# cc1200_wisun_st.net
KiCad netlist of a schematic drawn in Altium Designer
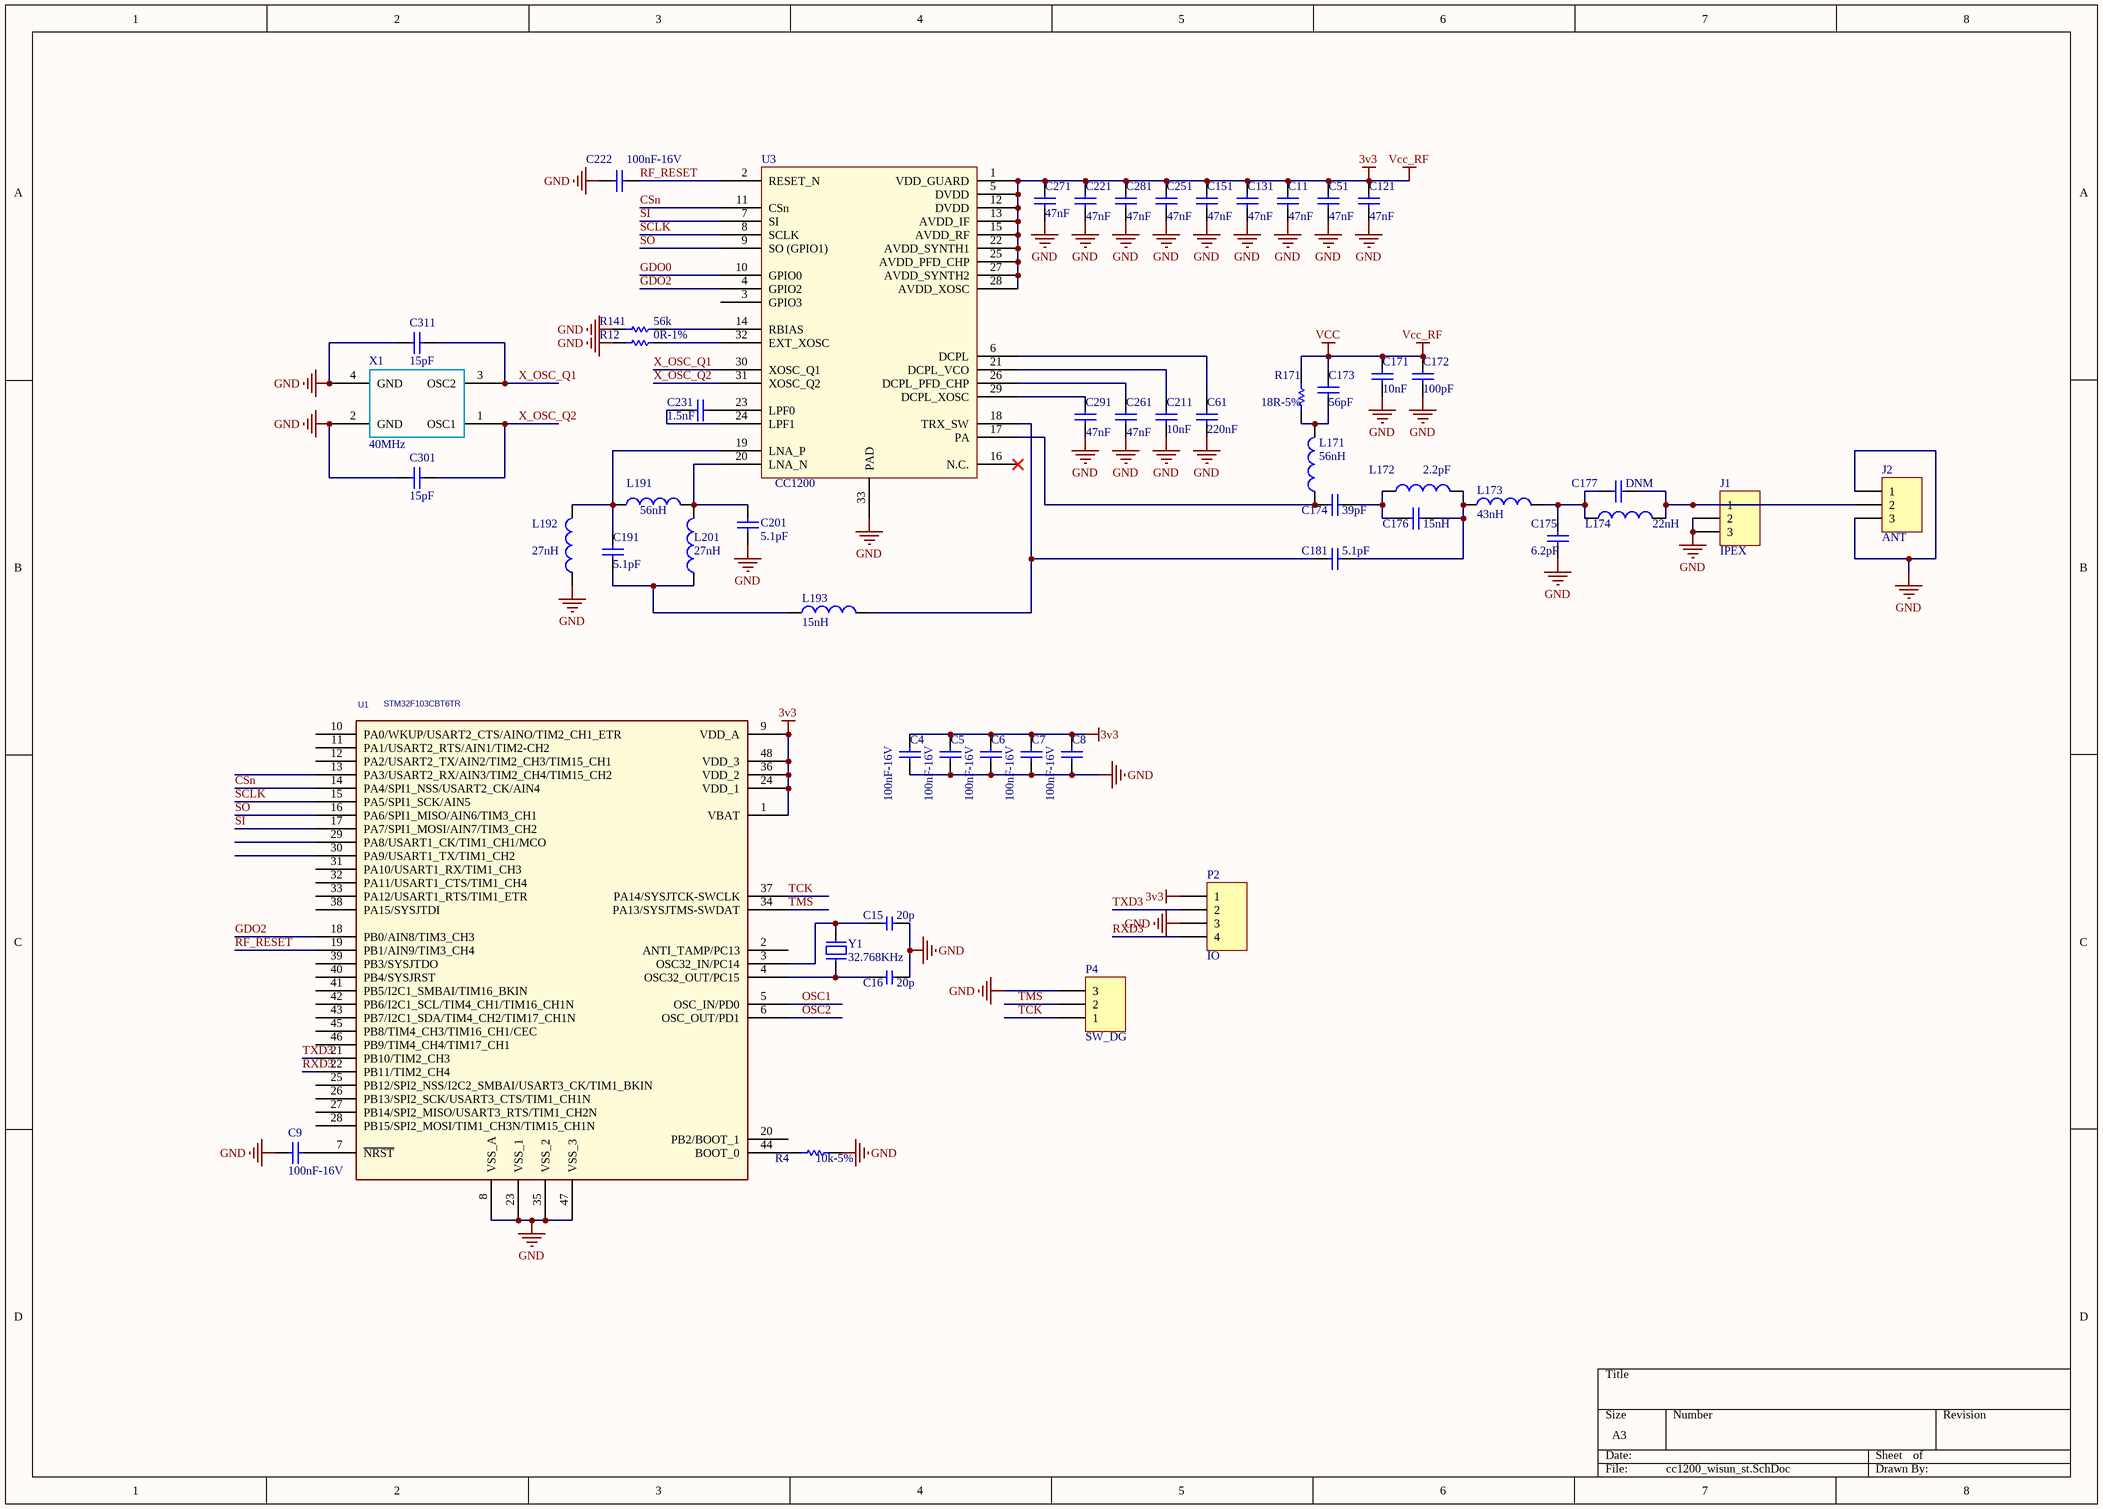
[diagram p0: cc1200_wisun_st.SchDoc]

(export (version "E")
  (design (tool "Eeschema 10.0.6"))
  (components
    (comp (ref "C4")
      (value "100nF-16V")
      (footprint "C0402 - SMT - Rounded")
      (description "CAP CER 0.1UF 16V Y5V 0402")
      (fields (field (name "DIGI-KEY PART NUMBER") "311-1047-2-ND") (field (name "MANUFACTURER") "Yageo"))
      (libsource (lib "Capacitor_0402") (part "100nF-16V-C0402"))
    )
    (comp (ref "C5")
      (value "100nF-16V")
      (footprint "C0402 - SMT - Rounded")
      (description "CAP CER 0.1UF 16V Y5V 0402")
      (fields (field (name "DIGI-KEY PART NUMBER") "311-1047-2-ND") (field (name "MANUFACTURER") "Yageo"))
      (libsource (lib "Capacitor_0402") (part "100nF-16V-C0402"))
    )
    (comp (ref "C6")
      (value "100nF-16V")
      (footprint "C0402 - SMT - Rounded")
      (description "CAP CER 0.1UF 16V Y5V 0402")
      (fields (field (name "DIGI-KEY PART NUMBER") "311-1047-2-ND") (field (name "MANUFACTURER") "Yageo"))
      (libsource (lib "Capacitor_0402") (part "100nF-16V-C0402"))
    )
    (comp (ref "C7")
      (value "100nF-16V")
      (footprint "C0402 - SMT - Rounded")
      (description "CAP CER 0.1UF 16V Y5V 0402")
      (fields (field (name "DIGI-KEY PART NUMBER") "311-1047-2-ND") (field (name "MANUFACTURER") "Yageo"))
      (libsource (lib "Capacitor_0402") (part "100nF-16V-C0402"))
    )
    (comp (ref "C8")
      (value "100nF-16V")
      (footprint "C0402 - SMT - Rounded")
      (description "CAP CER 0.1UF 16V Y5V 0402")
      (fields (field (name "DIGI-KEY PART NUMBER") "311-1047-2-ND") (field (name "MANUFACTURER") "Yageo"))
      (libsource (lib "Capacitor_0402") (part "100nF-16V-C0402"))
    )
    (comp (ref "C9")
      (value "100nF-16V")
      (footprint "C0402 - SMT - Rounded")
      (description "CAP CER 0.1UF 16V Y5V 0402")
      (fields (field (name "DIGI-KEY PART NUMBER") "311-1047-2-ND") (field (name "MANUFACTURER") "Yageo"))
      (libsource (lib "Capacitor_0402") (part "100nF-16V-C0402"))
    )
    (comp (ref "C11")
      (value "47nF")
      (footprint "C0402 - SMT - Rounded")
      (description "CAP CER 0.047UF 16V 10% X7R 0402")
      (fields (field (name "DIGI-KEY PART NUMBER") "311-1362-2-ND") (field (name "MANUFACTURER") "Yageo"))
      (libsource (lib "Capacitor_0402") (part "0.047µF-16V-C0402-10%"))
    )
    (comp (ref "C15") (value "20p") (footprint "C0402 - SMT - Rounded") (libsource (lib "*") (part "C_Dup1")))
    (comp (ref "C16") (value "20p") (footprint "C0402 - SMT - Rounded") (libsource (lib "*") (part "C_Dup1")))
    (comp (ref "C51")
      (value "47nF")
      (footprint "C0402 - SMT - Rounded")
      (description "CAP CER 0.047UF 16V 10% X7R 0402")
      (fields (field (name "DIGI-KEY PART NUMBER") "311-1362-2-ND") (field (name "MANUFACTURER") "Yageo"))
      (libsource (lib "Capacitor_0402") (part "0.047µF-16V-C0402-10%"))
    )
    (comp (ref "C61")
      (value "220nF")
      (footprint "C0402 - SMT - Rounded")
      (description "CAP CER 0.22UF 10V 10% X5R 0402")
      (fields (field (name "DIGI-KEY PART NUMBER") "311-1421-2-ND") (field (name "MANUFACTURER") "Yageo"))
      (libsource (lib "Capacitor_0402") (part "0.22µF-10V-C0402-10%"))
    )
    (comp (ref "C121")
      (value "47nF")
      (footprint "C0402 - SMT - Rounded")
      (description "CAP CER 0.047UF 16V 10% X7R 0402")
      (fields (field (name "DIGI-KEY PART NUMBER") "311-1362-2-ND") (field (name "MANUFACTURER") "Yageo"))
      (libsource (lib "Capacitor_0402") (part "0.047µF-16V-C0402-10%"))
    )
    (comp (ref "C131")
      (value "47nF")
      (footprint "C0402 - SMT - Rounded")
      (description "CAP CER 0.047UF 16V 10% X7R 0402")
      (fields (field (name "DIGI-KEY PART NUMBER") "311-1362-2-ND") (field (name "MANUFACTURER") "Yageo"))
      (libsource (lib "Capacitor_0402") (part "0.047µF-16V-C0402-10%"))
    )
    (comp (ref "C151")
      (value "47nF")
      (footprint "C0402 - SMT - Rounded")
      (description "CAP CER 0.047UF 16V 10% X7R 0402")
      (fields (field (name "DIGI-KEY PART NUMBER") "311-1362-2-ND") (field (name "MANUFACTURER") "Yageo"))
      (libsource (lib "Capacitor_0402") (part "0.047µF-16V-C0402-10%"))
    )
    (comp (ref "C171")
      (value "10nF")
      (footprint "C0402 - SMT - Rounded")
      (description "CAP CER 10000PF 25V X7R 0402")
      (fields
        (field (name "DIGI-KEY PART NUMBER") "490-1312-2-ND")
        (field (name "MANUFACTURER") "Murata Electronics North America")
      )
      (libsource (lib "Capacitor_0402") (part "5.0pF-50V-C0402-0.25pF"))
    )
    (comp (ref "C172")
      (value "100pF")
      (footprint "C0402 - SMT - Rounded")
      (description "CAP CER 100PF 50V NP0 0402")
      (fields
        (field (name "DIGI-KEY PART NUMBER") "490-5922-2-ND")
        (field (name "MANUFACTURER") "Murata Electronics North America")
      )
      (libsource (lib "Capacitor_0402") (part "5.0pF-50V-C0402-0.25pF"))
    )
    (comp (ref "C173")
      (value "56pF")
      (footprint "C0402 - SMT - Rounded")
      (description "CAP CER 56PF 50V NP0 0402")
      (fields
        (field (name "DIGI-KEY PART NUMBER") "490-1288-2-ND")
        (field (name "MANUFACTURER") "Murata Electronics North America")
      )
      (libsource (lib "Capacitor_0402") (part "5.0pF-50V-C0402-0.25pF"))
    )
    (comp (ref "C174")
      (value "39pF")
      (footprint "C0402 - SMT - Rounded")
      (description "CAP CER 39PF 50V NP0 0402")
      (fields
        (field (name "DIGI-KEY PART NUMBER") "490-5871-2-ND")
        (field (name "MANUFACTURER") "Murata Electronics North America")
      )
      (libsource (lib "Capacitor_0402") (part "5.0pF-50V-C0402-0.25pF"))
    )
    (comp (ref "C175")
      (value "6.2pF")
      (footprint "C0402 - SMT - Rounded")
      (description "CAP CER 6.2PF 50V NP0 0402")
      (fields
        (field (name "DIGI-KEY PART NUMBER") "490-11401-2-ND")
        (field (name "MANUFACTURER") "Murata Electronics North America")
      )
      (libsource (lib "Capacitor_0402") (part "5.0pF-50V-C0402-0.25pF"))
    )
    (comp (ref "C176")
      (value "2.2pF")
      (footprint "C0402 - SMT - Rounded")
      (description "CAP CER 2.2PF 50V NP0 0402")
      (fields
        (field (name "DIGI-KEY PART NUMBER") "490-5932-2-ND")
        (field (name "MANUFACTURER") "Murata Electronics North America")
      )
      (libsource (lib "Capacitor_0402") (part "5.0pF-50V-C0402-0.25pF"))
    )
    (comp (ref "C177")
      (value "DNM")
      (footprint "C0402 - SMT - Rounded")
      (description "CAP CER 1500PF 10V U2J 0402")
      (fields
        (field (name "DIGI-KEY PART NUMBER") "490-10690-2-ND")
        (field (name "MANUFACTURER") "Murata Electronics North America")
      )
      (libsource (lib "Capacitor_0402") (part "5.0pF-50V-C0402-0.25pF"))
    )
    (comp (ref "C181")
      (value "5.1pF")
      (footprint "C0402 - SMT - Rounded")
      (description "CAP CER 5.1PF 50V NP0 0402")
      (fields
        (field (name "DIGI-KEY PART NUMBER") "490-8216-2-ND")
        (field (name "MANUFACTURER") "Murata Electronics North America")
      )
      (libsource (lib "Capacitor_0402") (part "5.0pF-50V-C0402-0.25pF"))
    )
    (comp (ref "C191")
      (value "5.1pF")
      (footprint "C0402 - SMT - Rounded")
      (description "CAP CER 5.1PF 50V NP0 0402")
      (fields
        (field (name "DIGI-KEY PART NUMBER") "490-8216-2-ND")
        (field (name "MANUFACTURER") "Murata Electronics North America")
      )
      (libsource (lib "Capacitor_0402") (part "5.0pF-50V-C0402-0.25pF"))
    )
    (comp (ref "C201")
      (value "5.1pF")
      (footprint "C0402 - SMT - Rounded")
      (description "CAP CER 5.1PF 50V NP0 0402")
      (fields
        (field (name "DIGI-KEY PART NUMBER") "490-8216-2-ND")
        (field (name "MANUFACTURER") "Murata Electronics North America")
      )
      (libsource (lib "Capacitor_0402") (part "5.0pF-50V-C0402-0.25pF"))
    )
    (comp (ref "C211")
      (value "10nF")
      (footprint "C0402 - SMT - Rounded")
      (description "CAP CER 10000PF 16V 10% X7R 0402")
      (fields (field (name "DIGI-KEY PART NUMBER") "311-1042-2-ND") (field (name "MANUFACTURER") "Yageo"))
      (libsource (lib "Capacitor_0402") (part "10nF-16V-C0402-10%"))
    )
    (comp (ref "C221")
      (value "47nF")
      (footprint "C0402 - SMT - Rounded")
      (description "CAP CER 0.047UF 16V 10% X7R 0402")
      (fields (field (name "DIGI-KEY PART NUMBER") "311-1362-2-ND") (field (name "MANUFACTURER") "Yageo"))
      (libsource (lib "Capacitor_0402") (part "0.047µF-16V-C0402-10%"))
    )
    (comp (ref "C222")
      (value "100nF-16V")
      (footprint "C0402 - SMT - Rounded")
      (description "CAP CER 0.1UF 16V Y5V 0402")
      (fields (field (name "DIGI-KEY PART NUMBER") "311-1047-2-ND") (field (name "MANUFACTURER") "Yageo"))
      (libsource (lib "Capacitor_0402") (part "100nF-16V-C0402"))
    )
    (comp (ref "C231")
      (value "1.5nF")
      (footprint "C0402 - SMT - Rounded")
      (description "CAP CER 1500PF 50V 10% X7R 0402")
      (fields (field (name "DIGI-KEY PART NUMBER") "311-1032-2-ND") (field (name "MANUFACTURER") "Yageo"))
      (libsource (lib "Capacitor_0402") (part "1500pF-50V-C0402-10%"))
    )
    (comp (ref "C251")
      (value "47nF")
      (footprint "C0402 - SMT - Rounded")
      (description "CAP CER 0.047UF 16V 10% X7R 0402")
      (fields (field (name "DIGI-KEY PART NUMBER") "311-1362-2-ND") (field (name "MANUFACTURER") "Yageo"))
      (libsource (lib "Capacitor_0402") (part "0.047µF-16V-C0402-10%"))
    )
    (comp (ref "C261")
      (value "47nF")
      (footprint "C0402 - SMT - Rounded")
      (description "CAP CER 0.047UF 16V 10% X7R 0402")
      (fields (field (name "DIGI-KEY PART NUMBER") "311-1362-2-ND") (field (name "MANUFACTURER") "Yageo"))
      (libsource (lib "Capacitor_0402") (part "0.047µF-16V-C0402-10%"))
    )
    (comp (ref "C271")
      (value "47nF")
      (footprint "C0402 - SMT - Rounded")
      (description "CAP CER 0.047UF 16V 10% X7R 0402")
      (fields (field (name "DIGI-KEY PART NUMBER") "311-1362-2-ND") (field (name "MANUFACTURER") "Yageo"))
      (libsource (lib "Capacitor_0402") (part "0.047µF-16V-C0402-10%"))
    )
    (comp (ref "C281")
      (value "47nF")
      (footprint "C0402 - SMT - Rounded")
      (description "CAP CER 0.047UF 16V 10% X7R 0402")
      (fields (field (name "DIGI-KEY PART NUMBER") "311-1362-2-ND") (field (name "MANUFACTURER") "Yageo"))
      (libsource (lib "Capacitor_0402") (part "0.047µF-16V-C0402-10%"))
    )
    (comp (ref "C291")
      (value "47nF")
      (footprint "C0402 - SMT - Rounded")
      (description "CAP CER 0.047UF 16V 10% X7R 0402")
      (fields (field (name "DIGI-KEY PART NUMBER") "311-1362-2-ND") (field (name "MANUFACTURER") "Yageo"))
      (libsource (lib "Capacitor_0402") (part "0.047µF-16V-C0402-10%"))
    )
    (comp (ref "C301")
      (value "15pF")
      (footprint "C0402 - SMT - Rounded")
      (description "CAP CER 15PF 50V NP0 0402")
      (fields
        (field (name "DIGI-KEY PART NUMBER") "490-5888-2-ND")
        (field (name "MANUFACTURER") "Murata Electronics North America")
      )
      (libsource (lib "Capacitor_0402") (part "15pF-50V-C0402-5%"))
    )
    (comp (ref "C311")
      (value "15pF")
      (footprint "C0402 - SMT - Rounded")
      (description "CAP CER 15PF 50V NP0 0402")
      (fields
        (field (name "DIGI-KEY PART NUMBER") "490-5888-2-ND")
        (field (name "MANUFACTURER") "Murata Electronics North America")
      )
      (libsource (lib "Capacitor_0402") (part "15pF-50V-C0402-5%"))
    )
    (comp (ref "J1")
      (value "IPEX")
      (footprint "IPEX")
      (description "Header, 3-Pin")
      (fields (field (name "PUBLISHER") "Altium Limited"))
      (libsource (lib "Miscellaneous Connectors") (part "Header 3"))
    )
    (comp (ref "J2")
      (value "ANT")
      (footprint "ANT")
      (description "Header, 3-Pin")
      (fields (field (name "PUBLISHER") "Altium Limited"))
      (libsource (lib "Miscellaneous Connectors") (part "Header 3"))
    )
    (comp (ref "L171")
      (value "56nH")
      (footprint "L0402 - SMT - Rounded")
      (description "FIXED IND 56NH 200MA 1.17 OHM")
      (fields
        (field (name "DIGI-KEY PART NUMBER") "490-1155-2-ND")
        (field (name "MANUFACTURER") "Murata Electronics North America")
      )
      (libsource (lib "Inductor") (part "8.2nH-500mA-0402"))
    )
    (comp (ref "L172")
      (value "15nH")
      (footprint "L0402 - SMT - Rounded")
      (description "FIXED IND 15NH 460MA 160 MOHM")
      (fields
        (field (name "DIGI-KEY PART NUMBER") "490-1148-2-ND")
        (field (name "MANUFACTURER") "Murata Electronics North America")
      )
      (libsource (lib "Inductor") (part "8.2nH-500mA-0402"))
    )
    (comp (ref "L173")
      (value "43nH")
      (footprint "L0402 - SMT - Rounded")
      (description "FIXED IND 43NH 250MA 700 MOHM")
      (fields
        (field (name "DIGI-KEY PART NUMBER") "490-6818-2-ND")
        (field (name "MANUFACTURER") "Murata Electronics North America")
      )
      (libsource (lib "Inductor") (part "8.2nH-500mA-0402"))
    )
    (comp (ref "L174")
      (value "22nH")
      (footprint "L0402 - SMT - Rounded")
      (description "FIXED IND 22NH 310MA 300 MOHM")
      (fields
        (field (name "DIGI-KEY PART NUMBER") "490-1150-2-ND")
        (field (name "MANUFACTURER") "Murata Electronics North America")
      )
      (libsource (lib "Inductor") (part "8.2nH-500mA-0402"))
    )
    (comp (ref "L191")
      (value "56nH")
      (footprint "L0402 - SMT - Rounded")
      (description "FIXED IND 56NH 200MA 1.17 OHM")
      (fields
        (field (name "DIGI-KEY PART NUMBER") "490-1155-2-ND")
        (field (name "MANUFACTURER") "Murata Electronics North America")
      )
      (libsource (lib "Inductor") (part "8.2nH-500mA-0402"))
    )
    (comp (ref "L192")
      (value "27nH")
      (footprint "L0402 - SMT - Rounded")
      (description "FIXED IND 27NH 280MA 520 MOHM")
      (fields
        (field (name "DIGI-KEY PART NUMBER") "490-1151-2-ND")
        (field (name "MANUFACTURER") "Murata Electronics North America")
      )
      (libsource (lib "Inductor") (part "8.2nH-500mA-0402"))
    )
    (comp (ref "L193")
      (value "15nH")
      (footprint "L0402 - SMT - Rounded")
      (description "FIXED IND 15NH 460MA 160 MOHM")
      (fields
        (field (name "DIGI-KEY PART NUMBER") "490-1148-2-ND")
        (field (name "MANUFACTURER") "Murata Electronics North America")
      )
      (libsource (lib "Inductor") (part "8.2nH-500mA-0402"))
    )
    (comp (ref "L201")
      (value "27nH")
      (footprint "L0402 - SMT - Rounded")
      (description "FIXED IND 27NH 280MA 520 MOHM")
      (fields
        (field (name "DIGI-KEY PART NUMBER") "490-1151-2-ND")
        (field (name "MANUFACTURER") "Murata Electronics North America")
      )
      (libsource (lib "Inductor") (part "8.2nH-500mA-0402"))
    )
    (comp (ref "P2")
      (value "IO")
      (footprint "HDR1X4")
      (description "Header, 4-Pin")
      (fields (field (name "PUBLISHER") "Altium Limited"))
      (libsource (lib "Miscellaneous Connectors") (part "Header 4"))
    )
    (comp (ref "P4")
      (value "SW_DG")
      (footprint "HDR1X3")
      (description "Header, 3-Pin")
      (fields (field (name "PUBLISHER") "Altium Limited"))
      (libsource (lib "") (part "Header 3_1"))
    )
    (comp (ref "R4")
      (value "10k-5%")
      (footprint "R0402 - SMT - Rounded")
      (description "RES 10K OHM 1/16W 5% 0402 SMD")
      (fields
        (field (name "DIGI-KEY PART NUMBER") "311-10KJRCT-ND")
        (field (name "MANUFACTURER") "Yageo")
        (field (name "PUBLISHER") "Altium Limited")
      )
      (libsource (lib "Miscellaneous Devices") (part "Res1"))
    )
    (comp (ref "R12")
      (value "0R-1%")
      (footprint "R0402 - SMT - Rounded")
      (description "RES .10 OHM 1/16W 1% 0402 SMD")
      (fields (field (name "DIGI-KEY PART NUMBER") "311-.10PTR-ND") (field (name "MANUFACTURER") "Yageo"))
      (libsource (lib "Resistor_0402") (part "0.1R-1%-R0402"))
    )
    (comp (ref "R141")
      (value "56k")
      (footprint "R0402 - SMT - Rounded")
      (description "RES SMD 56K OHM 1% 1/16W 0402")
      (fields (field (name "DIGI-KEY PART NUMBER") "311-56.0KLRTR-ND") (field (name "MANUFACTURER") "Yageo"))
      (libsource (lib "Miscellaneous Devices") (part "Res1"))
    )
    (comp (ref "R171")
      (value "18R-5%")
      (footprint "R0402 - SMT - Rounded")
      (description "RES 18 OHM 1/16W 5% 0402 SMD")
      (fields (field (name "DIGI-KEY PART NUMBER") "311-18JRTR-ND") (field (name "MANUFACTURER") "Yageo"))
      (libsource (lib "Resistor_0402") (part "18R-5%-R0402"))
    )
    (comp (ref "U1")
      (value "STM32F103CBT6TR")
      (footprint "TQFP-48-P0.5")
      (description "MCU ARM 128K FLASH/TIMER")
      (fields
        (field (name "DIGI-KEY PART NUMBER") "497-6288-ND")
        (field (name "MANUFACTURER") "STMicroelectronics")
      )
      (libsource (lib "*") (part "ATmega128_4"))
    )
    (comp (ref "U3")
      (value "CC1200")
      (footprint "QFN-32M")
      (libsource (lib "Tuyens Library for Altium Designer") (part "CC1200"))
    )
    (comp (ref "X1")
      (value "40MHz")
      (footprint "CRYSTAL-2.5x2-4")
      (description "40MHz ±10ppm Crystal 10pF 50 Ohm -40°C ~ 85°C Surface Mount 4-SMD, No Lead (DFN, LCC)")
      (fields (field (name "DIGI-KEY PART NUMBER") "644-1249-2-ND") (field (name "MANUFACTURER") "NDK"))
      (libsource (lib "Tuyens Library for Altium Designer") (part "ZTA Crystal Resonator"))
    )
    (comp (ref "Y1")
      (value "32.768KHz")
      (footprint "Crystal-3.2x1.5")
      (description "Crystal 32.768KHz")
      (libsource (lib "tranhieu_hcmut") (part "XT32.768"))
    )
  )
  (nets
    (net (code "1") (name "/CSn") (class "Default")
      (node (ref "U1") (pin "14") (pinfunction "PA4/SPI1_NSS/USART2_CK/AIN4_14") (pintype "passive"))
      (node (ref "U3") (pin "11") (pinfunction "CSn_11") (pintype "passive"))
    )
    (net (code "2") (name "/GDO0") (class "Default")
      (node (ref "U3") (pin "10") (pinfunction "GPIO0_10") (pintype "passive"))
    )
    (net (code "3") (name "/GDO2") (class "Default")
      (node (ref "U1") (pin "18") (pinfunction "PB0/AIN8/TIM3_CH3_18") (pintype "passive"))
      (node (ref "U3") (pin "4") (pinfunction "GPIO2_4") (pintype "passive"))
    )
    (net (code "4") (name "/OSC1") (class "Default")
      (node (ref "U1") (pin "5") (pinfunction "OSC_IN/PD0_5") (pintype "passive"))
    )
    (net (code "5") (name "/OSC2") (class "Default")
      (node (ref "U1") (pin "6") (pinfunction "OSC_OUT/PD1_6") (pintype "passive"))
    )
    (net (code "6") (name "/RF_RESET") (class "Default")
      (node (ref "C222") (pin "2") (pinfunction "2_2") (pintype "passive"))
      (node (ref "U1") (pin "19") (pinfunction "PB1/AIN9/TIM3_CH4_19") (pintype "passive"))
      (node (ref "U3") (pin "2") (pinfunction "RESET_N_2") (pintype "passive"))
    )
    (net (code "7") (name "/RXD3") (class "Default")
      (node (ref "P2") (pin "4") (pinfunction "4_4") (pintype "passive"))
      (node (ref "U1") (pin "22") (pinfunction "PB11/TIM2_CH4_22") (pintype "passive"))
    )
    (net (code "8") (name "/SCLK") (class "Default")
      (node (ref "U1") (pin "15") (pinfunction "PA5/SPI1_SCK/AIN5_15") (pintype "passive"))
      (node (ref "U3") (pin "8") (pinfunction "SCLK_8") (pintype "passive"))
    )
    (net (code "9") (name "/SI") (class "Default")
      (node (ref "U1") (pin "17") (pinfunction "PA7/SPI1_MOSI/AIN7/TIM3_CH2_17") (pintype "passive"))
      (node (ref "U3") (pin "7") (pinfunction "SI_7") (pintype "passive"))
    )
    (net (code "10") (name "/SO") (class "Default")
      (node (ref "U1") (pin "16") (pinfunction "PA6/SPI1_MISO/AIN6/TIM3_CH1_16") (pintype "passive"))
      (node (ref "U3") (pin "9") (pinfunction "SO_(GPIO1)_9") (pintype "passive"))
    )
    (net (code "11") (name "/TCK") (class "Default")
      (node (ref "P4") (pin "1") (pinfunction "1_1") (pintype "passive"))
      (node (ref "U1") (pin "37") (pinfunction "PA14/SYSJTCK-SWCLK_37") (pintype "passive"))
    )
    (net (code "12") (name "/TMS") (class "Default")
      (node (ref "P4") (pin "2") (pinfunction "2_2") (pintype "passive"))
      (node (ref "U1") (pin "34") (pinfunction "PA13/SYSJTMS-SWDAT_34") (pintype "passive"))
    )
    (net (code "13") (name "/TXD3") (class "Default")
      (node (ref "P2") (pin "2") (pinfunction "2_2") (pintype "passive"))
      (node (ref "U1") (pin "21") (pinfunction "PB10/TIM2_CH3_21") (pintype "passive"))
    )
    (net (code "14") (name "/X_OSC_Q1") (class "Default")
      (node (ref "C311") (pin "1") (pinfunction "1_1") (pintype "passive"))
      (node (ref "U3") (pin "30") (pinfunction "XOSC_Q1_30") (pintype "passive"))
      (node (ref "X1") (pin "3") (pinfunction "OSC2_3") (pintype "passive"))
    )
    (net (code "15") (name "/X_OSC_Q2") (class "Default")
      (node (ref "C301") (pin "1") (pinfunction "1_1") (pintype "passive"))
      (node (ref "U3") (pin "31") (pinfunction "XOSC_Q2_31") (pintype "passive"))
      (node (ref "X1") (pin "1") (pinfunction "OSC1_1") (pintype "passive"))
    )
    (net (code "16") (name "3v3") (class "Default")
      (node (ref "C11") (pin "2") (pinfunction "2_2") (pintype "passive"))
      (node (ref "C121") (pin "2") (pinfunction "2_2") (pintype "passive"))
      (node (ref "C131") (pin "2") (pinfunction "2_2") (pintype "passive"))
      (node (ref "C151") (pin "2") (pinfunction "2_2") (pintype "passive"))
      (node (ref "C171") (pin "2") (pinfunction "2_2") (pintype "passive"))
      (node (ref "C172") (pin "2") (pinfunction "2_2") (pintype "passive"))
      (node (ref "C173") (pin "2") (pinfunction "2_2") (pintype "passive"))
      (node (ref "C221") (pin "2") (pinfunction "2_2") (pintype "passive"))
      (node (ref "C251") (pin "2") (pinfunction "2_2") (pintype "passive"))
      (node (ref "C271") (pin "2") (pinfunction "2_2") (pintype "passive"))
      (node (ref "C281") (pin "2") (pinfunction "2_2") (pintype "passive"))
      (node (ref "C4") (pin "2") (pinfunction "2_2") (pintype "passive"))
      (node (ref "C5") (pin "2") (pinfunction "2_2") (pintype "passive"))
      (node (ref "C51") (pin "2") (pinfunction "2_2") (pintype "passive"))
      (node (ref "C6") (pin "2") (pinfunction "2_2") (pintype "passive"))
      (node (ref "C7") (pin "2") (pinfunction "2_2") (pintype "passive"))
      (node (ref "C8") (pin "2") (pinfunction "2_2") (pintype "passive"))
      (node (ref "P2") (pin "1") (pinfunction "1_1") (pintype "passive"))
      (node (ref "R171") (pin "2") (pinfunction "2_2") (pintype "passive"))
      (node (ref "U1") (pin "1") (pinfunction "VBAT_1") (pintype "passive"))
      (node (ref "U1") (pin "24") (pinfunction "VDD_1_24") (pintype "passive"))
      (node (ref "U1") (pin "36") (pinfunction "VDD_2_36") (pintype "passive"))
      (node (ref "U1") (pin "48") (pinfunction "VDD_3_48") (pintype "passive"))
      (node (ref "U1") (pin "9") (pinfunction "VDD_A_9") (pintype "passive"))
      (node (ref "U3") (pin "1") (pinfunction "VDD_GUARD_1") (pintype "passive"))
      (node (ref "U3") (pin "12") (pinfunction "DVDD_12") (pintype "passive"))
      (node (ref "U3") (pin "13") (pinfunction "AVDD_IF_13") (pintype "passive"))
      (node (ref "U3") (pin "15") (pinfunction "AVDD_RF_15") (pintype "passive"))
      (node (ref "U3") (pin "22") (pinfunction "AVDD_SYNTH1_22") (pintype "passive"))
      (node (ref "U3") (pin "25") (pinfunction "AVDD_PFD_CHP_25") (pintype "passive"))
      (node (ref "U3") (pin "27") (pinfunction "AVDD_SYNTH2_27") (pintype "passive"))
      (node (ref "U3") (pin "28") (pinfunction "AVDD_XOSC_28") (pintype "passive"))
      (node (ref "U3") (pin "5") (pinfunction "DVDD_5") (pintype "passive"))
    )
    (net (code "17") (name "GND") (class "Default")
      (node (ref "C11") (pin "1") (pinfunction "1_1") (pintype "passive"))
      (node (ref "C121") (pin "1") (pinfunction "1_1") (pintype "passive"))
      (node (ref "C131") (pin "1") (pinfunction "1_1") (pintype "passive"))
      (node (ref "C15") (pin "1") (pinfunction "1_1") (pintype "passive"))
      (node (ref "C151") (pin "1") (pinfunction "1_1") (pintype "passive"))
      (node (ref "C16") (pin "1") (pinfunction "1_1") (pintype "passive"))
      (node (ref "C171") (pin "1") (pinfunction "1_1") (pintype "passive"))
      (node (ref "C172") (pin "1") (pinfunction "1_1") (pintype "passive"))
      (node (ref "C175") (pin "2") (pinfunction "2_2") (pintype "passive"))
      (node (ref "C201") (pin "1") (pinfunction "1_1") (pintype "passive"))
      (node (ref "C211") (pin "1") (pinfunction "1_1") (pintype "passive"))
      (node (ref "C221") (pin "1") (pinfunction "1_1") (pintype "passive"))
      (node (ref "C222") (pin "1") (pinfunction "1_1") (pintype "passive"))
      (node (ref "C251") (pin "1") (pinfunction "1_1") (pintype "passive"))
      (node (ref "C261") (pin "1") (pinfunction "1_1") (pintype "passive"))
      (node (ref "C271") (pin "1") (pinfunction "1_1") (pintype "passive"))
      (node (ref "C281") (pin "1") (pinfunction "1_1") (pintype "passive"))
      (node (ref "C291") (pin "1") (pinfunction "1_1") (pintype "passive"))
      (node (ref "C301") (pin "2") (pinfunction "2_2") (pintype "passive"))
      (node (ref "C311") (pin "2") (pinfunction "2_2") (pintype "passive"))
      (node (ref "C4") (pin "1") (pinfunction "1_1") (pintype "passive"))
      (node (ref "C5") (pin "1") (pinfunction "1_1") (pintype "passive"))
      (node (ref "C51") (pin "1") (pinfunction "1_1") (pintype "passive"))
      (node (ref "C6") (pin "1") (pinfunction "1_1") (pintype "passive"))
      (node (ref "C61") (pin "1") (pinfunction "1_1") (pintype "passive"))
      (node (ref "C7") (pin "1") (pinfunction "1_1") (pintype "passive"))
      (node (ref "C8") (pin "1") (pinfunction "1_1") (pintype "passive"))
      (node (ref "C9") (pin "2") (pinfunction "2_2") (pintype "passive"))
      (node (ref "J1") (pin "2") (pinfunction "2_2") (pintype "passive"))
      (node (ref "J1") (pin "3") (pinfunction "3_3") (pintype "passive"))
      (node (ref "J2") (pin "1") (pinfunction "1_1") (pintype "passive"))
      (node (ref "J2") (pin "3") (pinfunction "3_3") (pintype "passive"))
      (node (ref "L192") (pin "1") (pinfunction "1_1") (pintype "passive"))
      (node (ref "P2") (pin "3") (pinfunction "3_3") (pintype "passive"))
      (node (ref "P4") (pin "3") (pinfunction "3_3") (pintype "passive"))
      (node (ref "R12") (pin "1") (pinfunction "1_1") (pintype "passive"))
      (node (ref "R141") (pin "2") (pinfunction "2_2") (pintype "passive"))
      (node (ref "R4") (pin "1") (pinfunction "1_1") (pintype "passive"))
      (node (ref "U1") (pin "23") (pinfunction "VSS_1_23") (pintype "passive"))
      (node (ref "U1") (pin "35") (pinfunction "VSS_2_35") (pintype "passive"))
      (node (ref "U1") (pin "47") (pinfunction "VSS_3_47") (pintype "passive"))
      (node (ref "U1") (pin "8") (pinfunction "VSS_A_8") (pintype "passive"))
      (node (ref "U3") (pin "33") (pinfunction "PAD_33") (pintype "passive"))
      (node (ref "X1") (pin "2") (pinfunction "GND_2") (pintype "passive"))
      (node (ref "X1") (pin "4") (pinfunction "GND_4") (pintype "passive"))
    )
    (net (code "18") (name "Net-(C173-Pad1)") (class "Default")
      (node (ref "C173") (pin "1") (pinfunction "1_1") (pintype "passive"))
      (node (ref "L171") (pin "2") (pinfunction "2_2") (pintype "passive"))
      (node (ref "R171") (pin "1") (pinfunction "1_1") (pintype "passive"))
    )
    (net (code "19") (name "Net-(C174-Pad1)") (class "Default")
      (node (ref "C174") (pin "1") (pinfunction "1_1") (pintype "passive"))
      (node (ref "C176") (pin "2") (pinfunction "2_2") (pintype "passive"))
      (node (ref "L172") (pin "1") (pinfunction "1_1") (pintype "passive"))
    )
    (net (code "20") (name "Net-(C175-Pad1)") (class "Default")
      (node (ref "C175") (pin "1") (pinfunction "1_1") (pintype "passive"))
      (node (ref "C177") (pin "2") (pinfunction "2_2") (pintype "passive"))
      (node (ref "L173") (pin "2") (pinfunction "2_2") (pintype "passive"))
      (node (ref "L174") (pin "1") (pinfunction "1_1") (pintype "passive"))
    )
    (net (code "21") (name "Net-(C176-Pad1)") (class "Default")
      (node (ref "C176") (pin "1") (pinfunction "1_1") (pintype "passive"))
      (node (ref "C181") (pin "1") (pinfunction "1_1") (pintype "passive"))
      (node (ref "L172") (pin "2") (pinfunction "2_2") (pintype "passive"))
      (node (ref "L173") (pin "1") (pinfunction "1_1") (pintype "passive"))
    )
    (net (code "22") (name "Net-(C177-Pad1)") (class "Default")
      (node (ref "C177") (pin "1") (pinfunction "1_1") (pintype "passive"))
      (node (ref "J1") (pin "1") (pinfunction "1_1") (pintype "passive"))
      (node (ref "J2") (pin "2") (pinfunction "2_2") (pintype "passive"))
      (node (ref "L174") (pin "2") (pinfunction "2_2") (pintype "passive"))
    )
    (net (code "23") (name "Net-(C191-Pad1)") (class "Default")
      (node (ref "C191") (pin "1") (pinfunction "1_1") (pintype "passive"))
      (node (ref "L193") (pin "1") (pinfunction "1_1") (pintype "passive"))
      (node (ref "L201") (pin "1") (pinfunction "1_1") (pintype "passive"))
    )
    (net (code "24") (name "Net-(U1-BOOT_0)") (class "Default")
      (node (ref "R4") (pin "2") (pinfunction "2_2") (pintype "passive"))
      (node (ref "U1") (pin "44") (pinfunction "BOOT_0_44") (pintype "passive"))
    )
    (net (code "25") (name "Net-(U1-OSC32_IN{slash}PC14)") (class "Default")
      (node (ref "C15") (pin "2") (pinfunction "2_2") (pintype "passive"))
      (node (ref "U1") (pin "3") (pinfunction "OSC32_IN/PC14_3") (pintype "passive"))
      (node (ref "Y1") (pin "2") (pinfunction "2_2") (pintype "passive"))
    )
    (net (code "26") (name "Net-(U1-OSC32_OUT{slash}PC15)") (class "Default")
      (node (ref "C16") (pin "2") (pinfunction "2_2") (pintype "passive"))
      (node (ref "U1") (pin "4") (pinfunction "OSC32_OUT/PC15_4") (pintype "passive"))
      (node (ref "Y1") (pin "1") (pinfunction "1_1") (pintype "passive"))
    )
    (net (code "27") (name "Net-(U1-~{NRST})") (class "Default")
      (node (ref "C9") (pin "1") (pinfunction "1_1") (pintype "passive"))
      (node (ref "U1") (pin "7") (pinfunction "~{NRST}_7") (pintype "passive"))
    )
    (net (code "28") (name "Net-(U3-DCPL)") (class "Default")
      (node (ref "C61") (pin "2") (pinfunction "2_2") (pintype "passive"))
      (node (ref "U3") (pin "6") (pinfunction "DCPL_6") (pintype "passive"))
    )
    (net (code "29") (name "Net-(U3-DCPL_PFD_CHP)") (class "Default")
      (node (ref "C261") (pin "2") (pinfunction "2_2") (pintype "passive"))
      (node (ref "U3") (pin "26") (pinfunction "DCPL_PFD_CHP_26") (pintype "passive"))
    )
    (net (code "30") (name "Net-(U3-DCPL_VCO)") (class "Default")
      (node (ref "C211") (pin "2") (pinfunction "2_2") (pintype "passive"))
      (node (ref "U3") (pin "21") (pinfunction "DCPL_VCO_21") (pintype "passive"))
    )
    (net (code "31") (name "Net-(U3-DCPL_XOSC)") (class "Default")
      (node (ref "C291") (pin "2") (pinfunction "2_2") (pintype "passive"))
      (node (ref "U3") (pin "29") (pinfunction "DCPL_XOSC_29") (pintype "passive"))
    )
    (net (code "32") (name "Net-(U3-EXT_XOSC)") (class "Default")
      (node (ref "R12") (pin "2") (pinfunction "2_2") (pintype "passive"))
      (node (ref "U3") (pin "32") (pinfunction "EXT_XOSC_32") (pintype "passive"))
    )
    (net (code "33") (name "Net-(U3-LNA_N)") (class "Default")
      (node (ref "C201") (pin "2") (pinfunction "2_2") (pintype "passive"))
      (node (ref "L191") (pin "2") (pinfunction "2_2") (pintype "passive"))
      (node (ref "L201") (pin "2") (pinfunction "2_2") (pintype "passive"))
      (node (ref "U3") (pin "20") (pinfunction "LNA_N_20") (pintype "passive"))
    )
    (net (code "34") (name "Net-(U3-LNA_P)") (class "Default")
      (node (ref "C191") (pin "2") (pinfunction "2_2") (pintype "passive"))
      (node (ref "L191") (pin "1") (pinfunction "1_1") (pintype "passive"))
      (node (ref "L192") (pin "2") (pinfunction "2_2") (pintype "passive"))
      (node (ref "U3") (pin "19") (pinfunction "LNA_P_19") (pintype "passive"))
    )
    (net (code "35") (name "Net-(U3-LPF0)") (class "Default")
      (node (ref "C231") (pin "2") (pinfunction "2_2") (pintype "passive"))
      (node (ref "U3") (pin "23") (pinfunction "LPF0_23") (pintype "passive"))
    )
    (net (code "36") (name "Net-(U3-LPF1)") (class "Default")
      (node (ref "C231") (pin "1") (pinfunction "1_1") (pintype "passive"))
      (node (ref "U3") (pin "24") (pinfunction "LPF1_24") (pintype "passive"))
    )
    (net (code "37") (name "Net-(U3-PA)") (class "Default")
      (node (ref "C174") (pin "2") (pinfunction "2_2") (pintype "passive"))
      (node (ref "L171") (pin "1") (pinfunction "1_1") (pintype "passive"))
      (node (ref "U3") (pin "17") (pinfunction "PA_17") (pintype "passive"))
    )
    (net (code "38") (name "Net-(U3-RBIAS)") (class "Default")
      (node (ref "R141") (pin "1") (pinfunction "1_1") (pintype "passive"))
      (node (ref "U3") (pin "14") (pinfunction "RBIAS_14") (pintype "passive"))
    )
    (net (code "39") (name "Net-(U3-TRX_SW)") (class "Default")
      (node (ref "C181") (pin "2") (pinfunction "2_2") (pintype "passive"))
      (node (ref "L193") (pin "2") (pinfunction "2_2") (pintype "passive"))
      (node (ref "U3") (pin "18") (pinfunction "TRX_SW_18") (pintype "passive"))
    )
    (net (code "40") (name "unconnected-(U1-ANTI_TAMP{slash}PC13-Pad2)") (class "Default")
      (node (ref "U1") (pin "2") (pinfunction "ANTI_TAMP/PC13_2") (pintype "passive"))
    )
    (net (code "41") (name "unconnected-(U1-PA0{slash}WKUP{slash}USART2_CTS{slash}AINO{slash}TIM2_CH1_ETR-Pad10)") (class "Default")
      (node (ref "U1") (pin "10") (pinfunction "PA0/WKUP/USART2_CTS/AINO/TIM2_CH1_ETR_10") (pintype "passive"))
    )
    (net (code "42") (name "unconnected-(U1-PA1{slash}USART2_RTS{slash}AIN1{slash}TIM2-CH2-Pad11)") (class "Default")
      (node (ref "U1") (pin "11") (pinfunction "PA1/USART2_RTS/AIN1/TIM2-CH2_11") (pintype "passive"))
    )
    (net (code "43") (name "unconnected-(U1-PA2{slash}USART2_TX{slash}AIN2{slash}TIM2_CH3{slash}TIM15_CH1-Pad12)") (class "Default")
      (node (ref "U1") (pin "12") (pinfunction "PA2/USART2_TX/AIN2/TIM2_CH3/TIM15_CH1_12") (pintype "passive"))
    )
    (net (code "44") (name "unconnected-(U1-PA3{slash}USART2_RX{slash}AIN3{slash}TIM2_CH4{slash}TIM15_CH2-Pad13)") (class "Default")
      (node (ref "U1") (pin "13") (pinfunction "PA3/USART2_RX/AIN3/TIM2_CH4/TIM15_CH2_13") (pintype "passive"))
    )
    (net (code "45") (name "unconnected-(U1-PA8{slash}USART1_CK{slash}TIM1_CH1{slash}MCO-Pad29)") (class "Default")
      (node (ref "U1") (pin "29") (pinfunction "PA8/USART1_CK/TIM1_CH1/MCO_29") (pintype "passive"))
    )
    (net (code "46") (name "unconnected-(U1-PA9{slash}USART1_TX{slash}TIM1_CH2-Pad30)") (class "Default")
      (node (ref "U1") (pin "30") (pinfunction "PA9/USART1_TX/TIM1_CH2_30") (pintype "passive"))
    )
    (net (code "47") (name "unconnected-(U1-PA10{slash}USART1_RX{slash}TIM1_CH3-Pad31)") (class "Default")
      (node (ref "U1") (pin "31") (pinfunction "PA10/USART1_RX/TIM1_CH3_31") (pintype "passive"))
    )
    (net (code "48") (name "unconnected-(U1-PA11{slash}USART1_CTS{slash}TIM1_CH4-Pad32)") (class "Default")
      (node (ref "U1") (pin "32") (pinfunction "PA11/USART1_CTS/TIM1_CH4_32") (pintype "passive"))
    )
    (net (code "49") (name "unconnected-(U1-PA12{slash}USART1_RTS{slash}TIM1_ETR-Pad33)") (class "Default")
      (node (ref "U1") (pin "33") (pinfunction "PA12/USART1_RTS/TIM1_ETR_33") (pintype "passive"))
    )
    (net (code "50") (name "unconnected-(U1-PA15{slash}SYSJTDI-Pad38)") (class "Default")
      (node (ref "U1") (pin "38") (pinfunction "PA15/SYSJTDI_38") (pintype "passive"))
    )
    (net (code "51") (name "unconnected-(U1-PB2{slash}BOOT_1-Pad20)") (class "Default")
      (node (ref "U1") (pin "20") (pinfunction "PB2/BOOT_1_20") (pintype "passive"))
    )
    (net (code "52") (name "unconnected-(U1-PB3{slash}SYSJTDO-Pad39)") (class "Default")
      (node (ref "U1") (pin "39") (pinfunction "PB3/SYSJTDO_39") (pintype "passive"))
    )
    (net (code "53") (name "unconnected-(U1-PB4{slash}SYSJRST-Pad40)") (class "Default")
      (node (ref "U1") (pin "40") (pinfunction "PB4/SYSJRST_40") (pintype "passive"))
    )
    (net (code "54") (name "unconnected-(U1-PB5{slash}I2C1_SMBAI{slash}TIM16_BKIN-Pad41)") (class "Default")
      (node (ref "U1") (pin "41") (pinfunction "PB5/I2C1_SMBAI/TIM16_BKIN_41") (pintype "passive"))
    )
    (net (code "55") (name "unconnected-(U1-PB6{slash}I2C1_SCL{slash}TIM4_CH1{slash}TIM16_CH1N-Pad42)") (class "Default")
      (node (ref "U1") (pin "42") (pinfunction "PB6/I2C1_SCL/TIM4_CH1/TIM16_CH1N_42") (pintype "passive"))
    )
    (net (code "56") (name "unconnected-(U1-PB7{slash}I2C1_SDA{slash}TIM4_CH2{slash}TIM17_CH1N-Pad43)") (class "Default")
      (node (ref "U1") (pin "43") (pinfunction "PB7/I2C1_SDA/TIM4_CH2/TIM17_CH1N_43") (pintype "passive"))
    )
    (net (code "57") (name "unconnected-(U1-PB8{slash}TIM4_CH3{slash}TIM16_CH1{slash}CEC-Pad45)") (class "Default")
      (node (ref "U1") (pin "45") (pinfunction "PB8/TIM4_CH3/TIM16_CH1/CEC_45") (pintype "passive"))
    )
    (net (code "58") (name "unconnected-(U1-PB9{slash}TIM4_CH4{slash}TIM17_CH1-Pad46)") (class "Default")
      (node (ref "U1") (pin "46") (pinfunction "PB9/TIM4_CH4/TIM17_CH1_46") (pintype "passive"))
    )
    (net (code "59") (name "unconnected-(U1-PB12{slash}SPI2_NSS{slash}I2C2_SMBAI{slash}USART3_CK{slash}TIM1_BKIN-Pad25)") (class "Default")
      (node (ref "U1") (pin "25") (pinfunction "PB12/SPI2_NSS/I2C2_SMBAI/USART3_CK/TIM1_BKIN_25") (pintype "passive"))
    )
    (net (code "60") (name "unconnected-(U1-PB13{slash}SPI2_SCK{slash}USART3_CTS{slash}TIM1_CH1N-Pad26)") (class "Default")
      (node (ref "U1") (pin "26") (pinfunction "PB13/SPI2_SCK/USART3_CTS/TIM1_CH1N_26") (pintype "passive"))
    )
    (net (code "61") (name "unconnected-(U1-PB14{slash}SPI2_MISO{slash}USART3_RTS{slash}TIM1_CH2N-Pad27)") (class "Default")
      (node (ref "U1") (pin "27") (pinfunction "PB14/SPI2_MISO/USART3_RTS/TIM1_CH2N_27") (pintype "passive"))
    )
    (net (code "62") (name "unconnected-(U1-PB15{slash}SPI2_MOSI{slash}TIM1_CH3N{slash}TIM15_CH1N-Pad28)") (class "Default")
      (node (ref "U1") (pin "28") (pinfunction "PB15/SPI2_MOSI/TIM1_CH3N/TIM15_CH1N_28") (pintype "passive"))
    )
    (net (code "63") (name "unconnected-(U3-GPIO3-Pad3)") (class "Default")
      (node (ref "U3") (pin "3") (pinfunction "GPIO3_3") (pintype "passive"))
    )
    (net (code "64") (name "unconnected-(U3-N.C.-Pad16)") (class "Default")
      (node (ref "U3") (pin "16") (pinfunction "N.C._16") (pintype "passive+no_connect"))
    )
  )
)
